# usain_bot_chasis.net
KiCad netlist of a schematic drawn in EAGLE
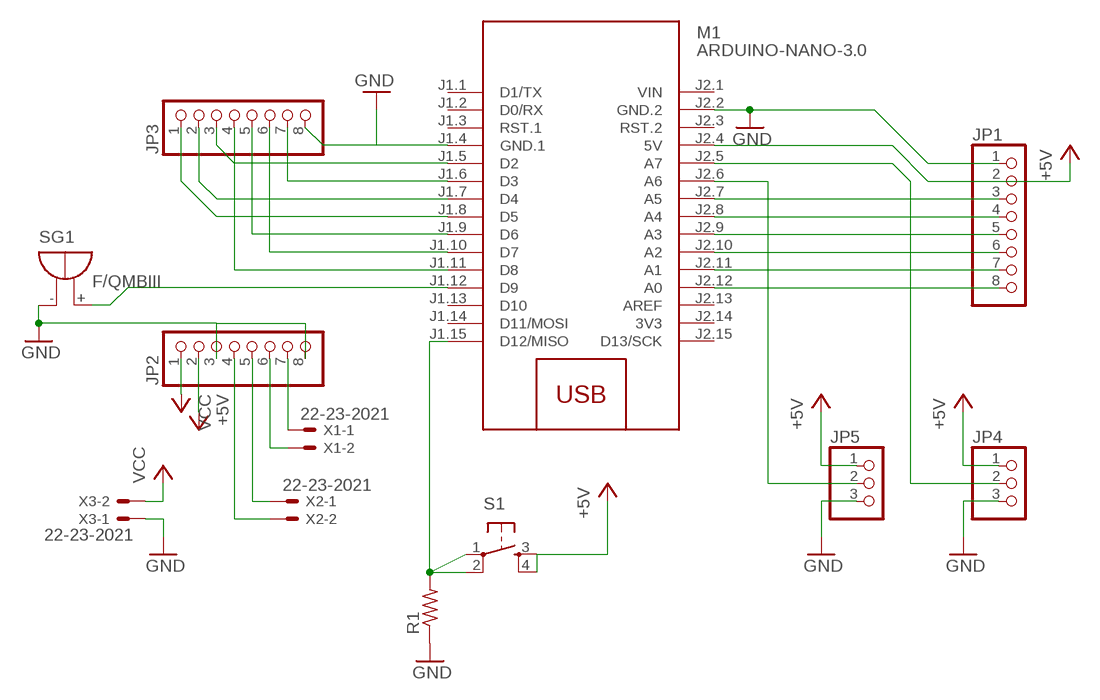
[diagram p0: schematic, sheet 1]

(export (version "E")
  (design (tool "Eeschema 10.0.6"))
  (components
    (comp (ref "JP1")
      (value "PINHD-1X8BIG")
      (footprint "eagle-import:1X08-BIG")
      (libsource (lib "eagle-import") (part "PINHD-1X8BIG"))
    )
    (comp (ref "JP2")
      (value "PINHD-1X8BIG")
      (footprint "eagle-import:1X08-BIG")
      (libsource (lib "eagle-import") (part "PINHD-1X8BIG"))
    )
    (comp (ref "JP3")
      (value "PINHD-1X8BIG")
      (footprint "eagle-import:1X08-BIG")
      (libsource (lib "eagle-import") (part "PINHD-1X8BIG"))
    )
    (comp (ref "JP4")
      (value "PINHD-1X3")
      (footprint "eagle-import:1X03")
      (libsource (lib "eagle-import") (part "PINHD-1X3"))
    )
    (comp (ref "JP5")
      (value "PINHD-1X3")
      (footprint "eagle-import:1X03")
      (libsource (lib "eagle-import") (part "PINHD-1X3"))
    )
    (comp (ref "M1")
      (value "ARDUINO-NANO-3.0")
      (footprint "eagle-import:ARDUINO-NANO-3.0")
      (libsource (lib "eagle-import") (part "ARDUINO-NANO-3.0"))
    )
    (comp (ref "R1")
      (value "R-US_0207/7")
      (footprint "eagle-import:0207_7")
      (libsource (lib "eagle-import") (part "R-US_0207/7"))
    )
    (comp (ref "S1")
      (value "TAC_SWITCHPTH")
      (footprint "eagle-import:TACTILE-PTH")
      (libsource (lib "eagle-import") (part "TAC_SWITCHPTH"))
    )
    (comp (ref "SG1")
      (value "F/QMBIII")
      (footprint "eagle-import:F_QMBIII")
      (libsource (lib "eagle-import") (part "F/QMBIII"))
    )
    (comp (ref "X1")
      (value "22-23-2021")
      (footprint "eagle-import:22-23-2021")
      (fields (field (name "MF") "MOLEX"))
      (libsource (lib "eagle-import") (part "22-23-2021"))
    )
    (comp (ref "X2")
      (value "22-23-2021")
      (footprint "eagle-import:22-23-2021")
      (fields (field (name "MF") "MOLEX"))
      (libsource (lib "eagle-import") (part "22-23-2021"))
    )
    (comp (ref "X3")
      (value "22-23-2021")
      (footprint "eagle-import:22-23-2021")
      (fields (field (name "MF") "MOLEX"))
      (libsource (lib "eagle-import") (part "22-23-2021"))
    )
  )
  (nets
    (net (code "1") (name "+5V") (class "Default")
      (node (ref "JP1") (pin "2") (pinfunction "2_2") (pintype "passive"))
      (node (ref "JP2") (pin "2") (pinfunction "2_2") (pintype "passive"))
      (node (ref "JP4") (pin "1") (pinfunction "1_1") (pintype "passive"))
      (node (ref "JP5") (pin "1") (pinfunction "1_1") (pintype "passive"))
      (node (ref "M1") (pin "J2.4") (pinfunction "5V_J2.4") (pintype "power_in"))
      (node (ref "S1") (pin "3") (pinfunction "3_3") (pintype "passive"))
      (node (ref "S1") (pin "4") (pinfunction "4_4") (pintype "passive"))
    )
    (net (code "2") (name "/3V3") (class "Default")
      (node (ref "M1") (pin "J2.14") (pinfunction "3V3_J2.14") (pintype "power_in"))
    )
    (net (code "3") (name "/VIN") (class "Default")
      (node (ref "M1") (pin "J2.1") (pinfunction "VIN_J2.1") (pintype "power_in"))
    )
    (net (code "4") (name "GND") (class "Default")
      (node (ref "JP1") (pin "1") (pinfunction "1_1") (pintype "passive"))
      (node (ref "JP2") (pin "3") (pinfunction "3_3") (pintype "passive"))
      (node (ref "JP2") (pin "8") (pinfunction "8_8") (pintype "passive"))
      (node (ref "JP3") (pin "8") (pinfunction "8_8") (pintype "passive"))
      (node (ref "JP4") (pin "3") (pinfunction "3_3") (pintype "passive"))
      (node (ref "JP5") (pin "3") (pinfunction "3_3") (pintype "passive"))
      (node (ref "M1") (pin "J1.4") (pinfunction "GND.1_J1.4") (pintype "power_in"))
      (node (ref "M1") (pin "J2.2") (pinfunction "GND.2_J2.2") (pintype "power_in"))
      (node (ref "R1") (pin "1") (pinfunction "1_1") (pintype "passive"))
      (node (ref "SG1") (pin "-") (pinfunction "+_-") (pintype "passive"))
      (node (ref "X3") (pin "1") (pinfunction "S_1") (pintype "passive"))
    )
    (net (code "5") (name "Net-(M1-A0)") (class "Default")
      (node (ref "JP1") (pin "8") (pinfunction "8_8") (pintype "passive"))
      (node (ref "M1") (pin "J2.12") (pinfunction "A0_J2.12") (pintype "bidirectional"))
    )
    (net (code "6") (name "Net-(M1-A1)") (class "Default")
      (node (ref "JP1") (pin "7") (pinfunction "7_7") (pintype "passive"))
      (node (ref "M1") (pin "J2.11") (pinfunction "A1_J2.11") (pintype "bidirectional"))
    )
    (net (code "7") (name "Net-(M1-A2)") (class "Default")
      (node (ref "JP1") (pin "6") (pinfunction "6_6") (pintype "passive"))
      (node (ref "M1") (pin "J2.10") (pinfunction "A2_J2.10") (pintype "bidirectional"))
    )
    (net (code "8") (name "Net-(M1-A3)") (class "Default")
      (node (ref "JP1") (pin "5") (pinfunction "5_5") (pintype "passive"))
      (node (ref "M1") (pin "J2.9") (pinfunction "A3_J2.9") (pintype "bidirectional"))
    )
    (net (code "9") (name "Net-(M1-A4)") (class "Default")
      (node (ref "JP1") (pin "4") (pinfunction "4_4") (pintype "passive"))
      (node (ref "M1") (pin "J2.8") (pinfunction "A4_J2.8") (pintype "bidirectional"))
    )
    (net (code "10") (name "Net-(M1-A5)") (class "Default")
      (node (ref "JP1") (pin "3") (pinfunction "3_3") (pintype "passive"))
      (node (ref "M1") (pin "J2.7") (pinfunction "A5_J2.7") (pintype "bidirectional"))
    )
    (net (code "11") (name "Net-(M1-A6)") (class "Default")
      (node (ref "JP5") (pin "2") (pinfunction "2_2") (pintype "passive"))
      (node (ref "M1") (pin "J2.6") (pinfunction "A6_J2.6") (pintype "bidirectional"))
    )
    (net (code "12") (name "Net-(M1-A7)") (class "Default")
      (node (ref "JP4") (pin "2") (pinfunction "2_2") (pintype "passive"))
      (node (ref "M1") (pin "J2.5") (pinfunction "A7_J2.5") (pintype "bidirectional"))
    )
    (net (code "13") (name "Net-(M1-D2)") (class "Default")
      (node (ref "JP3") (pin "3") (pinfunction "3_3") (pintype "passive"))
      (node (ref "M1") (pin "J1.5") (pinfunction "D2_J1.5") (pintype "bidirectional"))
    )
    (net (code "14") (name "Net-(M1-D3)") (class "Default")
      (node (ref "JP3") (pin "7") (pinfunction "7_7") (pintype "passive"))
      (node (ref "M1") (pin "J1.6") (pinfunction "D3_J1.6") (pintype "bidirectional"))
    )
    (net (code "15") (name "Net-(M1-D4)") (class "Default")
      (node (ref "JP3") (pin "2") (pinfunction "2_2") (pintype "passive"))
      (node (ref "M1") (pin "J1.7") (pinfunction "D4_J1.7") (pintype "bidirectional"))
    )
    (net (code "16") (name "Net-(M1-D5)") (class "Default")
      (node (ref "JP3") (pin "1") (pinfunction "1_1") (pintype "passive"))
      (node (ref "M1") (pin "J1.8") (pinfunction "D5_J1.8") (pintype "bidirectional"))
    )
    (net (code "17") (name "Net-(M1-D6)") (class "Default")
      (node (ref "JP3") (pin "5") (pinfunction "5_5") (pintype "passive"))
      (node (ref "M1") (pin "J1.9") (pinfunction "D6_J1.9") (pintype "bidirectional"))
    )
    (net (code "18") (name "Net-(M1-D7)") (class "Default")
      (node (ref "JP3") (pin "6") (pinfunction "6_6") (pintype "passive"))
      (node (ref "M1") (pin "J1.10") (pinfunction "D7_J1.10") (pintype "bidirectional"))
    )
    (net (code "19") (name "Net-(M1-D8)") (class "Default")
      (node (ref "JP3") (pin "4") (pinfunction "4_4") (pintype "passive"))
      (node (ref "M1") (pin "J1.11") (pinfunction "D8_J1.11") (pintype "bidirectional"))
    )
    (net (code "20") (name "Net-(M1-D9)") (class "Default")
      (node (ref "M1") (pin "J1.12") (pinfunction "D9_J1.12") (pintype "bidirectional"))
      (node (ref "SG1") (pin "+") (pinfunction "-_+") (pintype "passive"))
    )
    (net (code "21") (name "Net-(M1-D12{slash}MISO)") (class "Default")
      (node (ref "M1") (pin "J1.15") (pinfunction "D12/MISO_J1.15") (pintype "bidirectional"))
      (node (ref "R1") (pin "2") (pinfunction "2_2") (pintype "passive"))
      (node (ref "S1") (pin "1") (pinfunction "1_1") (pintype "passive"))
      (node (ref "S1") (pin "2") (pinfunction "2_2") (pintype "passive"))
    )
    (net (code "22") (name "Net-(X1A-S)") (class "Default")
      (node (ref "JP2") (pin "7") (pinfunction "7_7") (pintype "passive"))
      (node (ref "X1") (pin "1") (pinfunction "S_1") (pintype "passive"))
    )
    (net (code "23") (name "Net-(X1B-S)") (class "Default")
      (node (ref "JP2") (pin "6") (pinfunction "6_6") (pintype "passive"))
      (node (ref "X1") (pin "2") (pinfunction "S_2") (pintype "passive"))
    )
    (net (code "24") (name "Net-(X2A-S)") (class "Default")
      (node (ref "JP2") (pin "5") (pinfunction "5_5") (pintype "passive"))
      (node (ref "X2") (pin "1") (pinfunction "S_1") (pintype "passive"))
    )
    (net (code "25") (name "Net-(X2B-S)") (class "Default")
      (node (ref "JP2") (pin "4") (pinfunction "4_4") (pintype "passive"))
      (node (ref "X2") (pin "2") (pinfunction "S_2") (pintype "passive"))
    )
    (net (code "26") (name "VCC") (class "Default")
      (node (ref "JP2") (pin "1") (pinfunction "1_1") (pintype "passive"))
      (node (ref "X3") (pin "2") (pinfunction "S_2") (pintype "passive"))
    )
    (net (code "27") (name "unconnected-(M1-AREF-PadJ2.13)") (class "Default")
      (node (ref "M1") (pin "J2.13") (pinfunction "AREF_J2.13") (pintype "bidirectional"))
    )
    (net (code "28") (name "unconnected-(M1-D0{slash}RX-PadJ1.2)") (class "Default")
      (node (ref "M1") (pin "J1.2") (pinfunction "D0/RX_J1.2") (pintype "bidirectional"))
    )
    (net (code "29") (name "unconnected-(M1-D1{slash}TX-PadJ1.1)") (class "Default")
      (node (ref "M1") (pin "J1.1") (pinfunction "D1/TX_J1.1") (pintype "bidirectional"))
    )
    (net (code "30") (name "unconnected-(M1-D10-PadJ1.13)") (class "Default")
      (node (ref "M1") (pin "J1.13") (pinfunction "D10_J1.13") (pintype "bidirectional"))
    )
    (net (code "31") (name "unconnected-(M1-D11{slash}MOSI-PadJ1.14)") (class "Default")
      (node (ref "M1") (pin "J1.14") (pinfunction "D11/MOSI_J1.14") (pintype "bidirectional"))
    )
    (net (code "32") (name "unconnected-(M1-D13{slash}SCK-PadJ2.15)") (class "Default")
      (node (ref "M1") (pin "J2.15") (pinfunction "D13/SCK_J2.15") (pintype "bidirectional"))
    )
    (net (code "33") (name "unconnected-(M1-RST.1-PadJ1.3)") (class "Default")
      (node (ref "M1") (pin "J1.3") (pinfunction "RST.1_J1.3") (pintype "bidirectional"))
    )
    (net (code "34") (name "unconnected-(M1-RST.2-PadJ2.3)") (class "Default")
      (node (ref "M1") (pin "J2.3") (pinfunction "RST.2_J2.3") (pintype "bidirectional"))
    )
  )
)
